# bASEpLATE.net
KiCad netlist of a schematic drawn in EAGLE
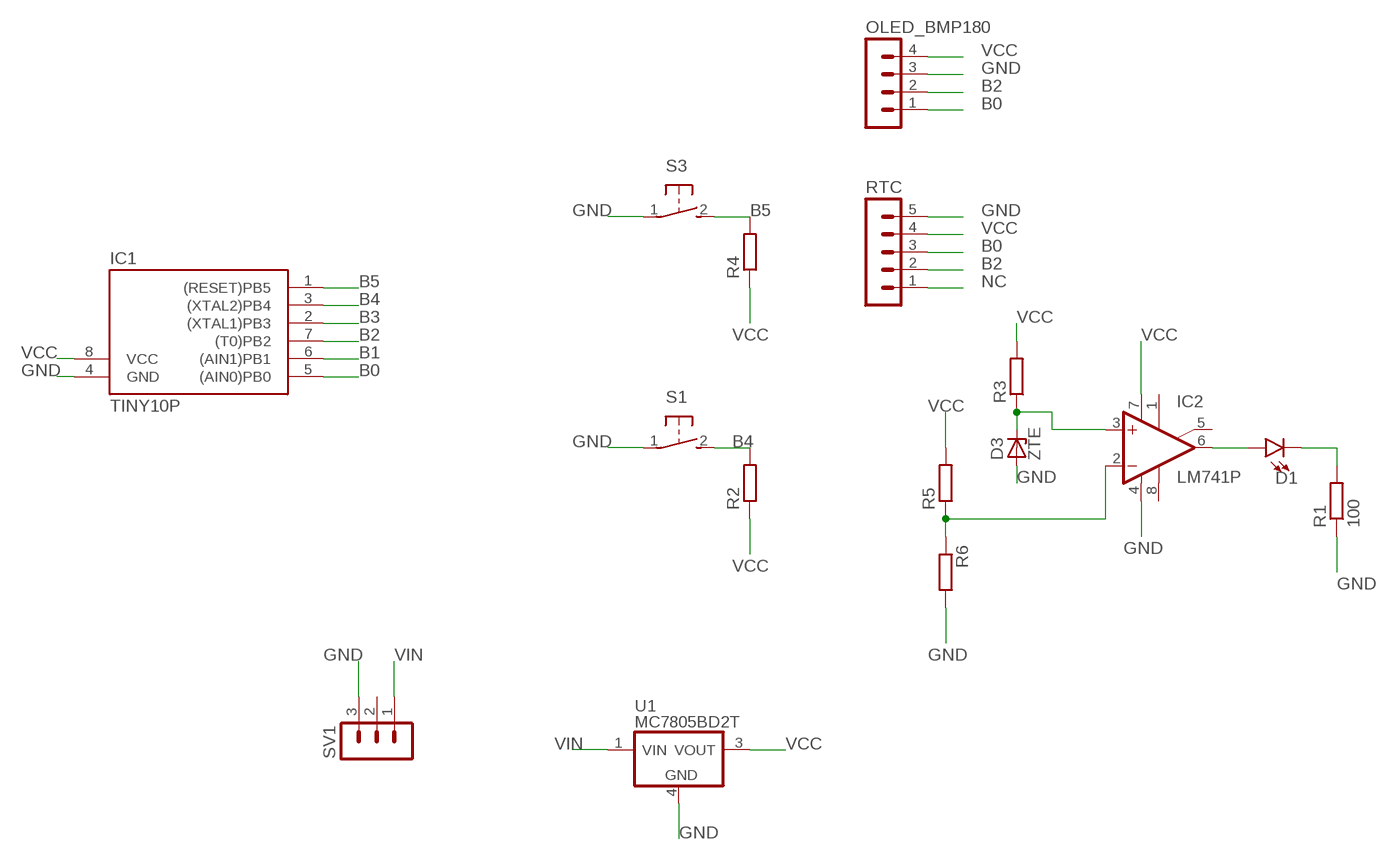
[diagram p0: schematic, sheet 1]

(export (version "E")
  (design (tool "Eeschema 10.0.6"))
  (components
    (comp (ref "D1")
      (value "LED-3MM-NO_SILK")
      (footprint "eagle-import:LED_3MM-NS")
      (libsource (lib "eagle-import") (part "LED-3MM-NO_SILK"))
    )
    (comp (ref "D3")
      (value "ZTE")
      (footprint "eagle-import:DO35Z10")
      (libsource (lib "eagle-import") (part "ZTE"))
    )
    (comp (ref "IC1")
      (value "TINY10P")
      (footprint "eagle-import:DIL08")
      (libsource (lib "eagle-import") (part "TINY10P"))
    )
    (comp (ref "IC2")
      (value "LM741P")
      (footprint "eagle-import:DIL08")
      (libsource (lib "eagle-import") (part "741PLM"))
    )
    (comp (ref "OLED_BMP180")
      (value "MA04-1")
      (footprint "eagle-import:MA04-1")
      (libsource (lib "eagle-import") (part "MA04-1"))
    )
    (comp (ref "R1")
      (value "100")
      (footprint "eagle-import:0204_7")
      (libsource (lib "eagle-import") (part "R-EU_0204/7"))
    )
    (comp (ref "R2")
      (value "R-EU_0204/7")
      (footprint "eagle-import:0204_7")
      (libsource (lib "eagle-import") (part "R-EU_0204/7"))
    )
    (comp (ref "R3")
      (value "R-EU_0204/7")
      (footprint "eagle-import:0204_7")
      (libsource (lib "eagle-import") (part "R-EU_0204/7"))
    )
    (comp (ref "R4")
      (value "R-EU_0204/7")
      (footprint "eagle-import:0204_7")
      (libsource (lib "eagle-import") (part "R-EU_0204/7"))
    )
    (comp (ref "R5")
      (value "R-EU_0204/7")
      (footprint "eagle-import:0204_7")
      (libsource (lib "eagle-import") (part "R-EU_0204/7"))
    )
    (comp (ref "R6")
      (value "R-EU_0204/7")
      (footprint "eagle-import:0204_7")
      (libsource (lib "eagle-import") (part "R-EU_0204/7"))
    )
    (comp (ref "RTC")
      (value "MA05-1")
      (footprint "eagle-import:MA05-1")
      (libsource (lib "eagle-import") (part "MA05-1"))
    )
    (comp (ref "S1")
      (value "31-XX")
      (footprint "eagle-import:B3F-31XX")
      (fields (field (name "MPN") "B3F-3100"))
      (libsource (lib "eagle-import") (part "31-XX"))
    )
    (comp (ref "S3")
      (value "31-XX")
      (footprint "eagle-import:B3F-31XX")
      (fields (field (name "MPN") "B3F-3100"))
      (libsource (lib "eagle-import") (part "31-XX"))
    )
    (comp (ref "SV1")
      (value "MA03-1")
      (footprint "eagle-import:MA03-1")
      (libsource (lib "eagle-import") (part "MA03-1"))
    )
    (comp (ref "U1")
      (value "MC7805BD2T")
      (footprint "eagle-import:D2PAK-3")
      (libsource (lib "eagle-import") (part "MC78D2T05B"))
    )
  )
  (nets
    (net (code "1") (name "/B0") (class "Default")
      (node (ref "IC1") (pin "5") (pinfunction "(AIN0)PB0_5") (pintype "bidirectional"))
      (node (ref "OLED_BMP180") (pin "1") (pinfunction "1_1") (pintype "passive"))
      (node (ref "RTC") (pin "3") (pinfunction "3_3") (pintype "passive"))
    )
    (net (code "2") (name "/B1") (class "Default")
      (node (ref "IC1") (pin "6") (pinfunction "(AIN1)PB1_6") (pintype "bidirectional"))
    )
    (net (code "3") (name "/B2") (class "Default")
      (node (ref "IC1") (pin "7") (pinfunction "(T0)PB2_7") (pintype "bidirectional"))
      (node (ref "OLED_BMP180") (pin "2") (pinfunction "2_2") (pintype "passive"))
      (node (ref "RTC") (pin "2") (pinfunction "2_2") (pintype "passive"))
    )
    (net (code "4") (name "/B3") (class "Default")
      (node (ref "IC1") (pin "2") (pinfunction "(XTAL1)PB3_2") (pintype "bidirectional"))
    )
    (net (code "5") (name "/B4") (class "Default")
      (node (ref "IC1") (pin "3") (pinfunction "(XTAL2)PB4_3") (pintype "bidirectional"))
      (node (ref "R2") (pin "2") (pinfunction "2_2") (pintype "passive"))
      (node (ref "S1") (pin "2") (pinfunction "S_2") (pintype "passive"))
    )
    (net (code "6") (name "/B5") (class "Default")
      (node (ref "IC1") (pin "1") (pinfunction "(RESET)PB5_1") (pintype "bidirectional"))
      (node (ref "R4") (pin "2") (pinfunction "2_2") (pintype "passive"))
      (node (ref "S3") (pin "2") (pinfunction "S_2") (pintype "passive"))
    )
    (net (code "7") (name "/GND") (class "Default")
      (node (ref "D3") (pin "A") (pinfunction "A_A") (pintype "passive"))
      (node (ref "IC1") (pin "4") (pinfunction "GND_4") (pintype "power_in"))
      (node (ref "IC2") (pin "4") (pinfunction "V-_4") (pintype "power_in"))
      (node (ref "OLED_BMP180") (pin "3") (pinfunction "3_3") (pintype "passive"))
      (node (ref "R1") (pin "1") (pinfunction "1_1") (pintype "passive"))
      (node (ref "R6") (pin "2") (pinfunction "2_2") (pintype "passive"))
      (node (ref "RTC") (pin "5") (pinfunction "5_5") (pintype "passive"))
      (node (ref "S1") (pin "1") (pinfunction "P_1") (pintype "passive"))
      (node (ref "S3") (pin "1") (pinfunction "P_1") (pintype "passive"))
      (node (ref "SV1") (pin "3") (pinfunction "3_3") (pintype "passive"))
      (node (ref "U1") (pin "4") (pinfunction "GND_4") (pintype "power_in"))
    )
    (net (code "8") (name "/NC") (class "Default")
      (node (ref "RTC") (pin "1") (pinfunction "1_1") (pintype "passive"))
    )
    (net (code "9") (name "/VCC") (class "Default")
      (node (ref "IC1") (pin "8") (pinfunction "VCC_8") (pintype "power_in"))
      (node (ref "IC2") (pin "7") (pinfunction "V+_7") (pintype "power_in"))
      (node (ref "OLED_BMP180") (pin "4") (pinfunction "4_4") (pintype "passive"))
      (node (ref "R2") (pin "1") (pinfunction "1_1") (pintype "passive"))
      (node (ref "R3") (pin "2") (pinfunction "2_2") (pintype "passive"))
      (node (ref "R4") (pin "1") (pinfunction "1_1") (pintype "passive"))
      (node (ref "R5") (pin "2") (pinfunction "2_2") (pintype "passive"))
      (node (ref "RTC") (pin "4") (pinfunction "4_4") (pintype "passive"))
      (node (ref "U1") (pin "3") (pinfunction "VOUT_3") (pintype "power_in"))
    )
    (net (code "10") (name "/VIN") (class "Default")
      (node (ref "SV1") (pin "1") (pinfunction "1_1") (pintype "passive"))
      (node (ref "U1") (pin "1") (pinfunction "VIN_1") (pintype "power_in"))
    )
    (net (code "11") (name "Net-(D1-C)") (class "Default")
      (node (ref "D1") (pin "K") (pinfunction "C_K") (pintype "passive"))
      (node (ref "R1") (pin "2") (pinfunction "2_2") (pintype "passive"))
    )
    (net (code "12") (name "Net-(IC2-+IN)") (class "Default")
      (node (ref "D3") (pin "C") (pinfunction "C_C") (pintype "passive"))
      (node (ref "IC2") (pin "3") (pinfunction "+IN_3") (pintype "input"))
      (node (ref "R3") (pin "1") (pinfunction "1_1") (pintype "passive"))
    )
    (net (code "13") (name "Net-(IC2--IN)") (class "Default")
      (node (ref "IC2") (pin "2") (pinfunction "-IN_2") (pintype "input"))
      (node (ref "R5") (pin "1") (pinfunction "1_1") (pintype "passive"))
      (node (ref "R6") (pin "1") (pinfunction "1_1") (pintype "passive"))
    )
    (net (code "14") (name "Net-(IC2-OUT)") (class "Default")
      (node (ref "D1") (pin "A") (pinfunction "A_A") (pintype "passive"))
      (node (ref "IC2") (pin "6") (pinfunction "OUT_6") (pintype "output"))
    )
    (net (code "15") (name "unconnected-(IC2-ON1-Pad1)") (class "Default")
      (node (ref "IC2") (pin "1") (pinfunction "ON1_1") (pintype "passive"))
    )
    (net (code "16") (name "unconnected-(IC2-ON2-Pad5)") (class "Default")
      (node (ref "IC2") (pin "5") (pinfunction "ON2_5") (pintype "passive"))
    )
    (net (code "17") (name "unconnected-(IC2-OPT-Pad8)") (class "Default")
      (node (ref "IC2") (pin "8") (pinfunction "OPT_8") (pintype "passive"))
    )
    (net (code "18") (name "unconnected-(SV1-Pad2)") (class "Default")
      (node (ref "SV1") (pin "2") (pinfunction "2_2") (pintype "passive"))
    )
  )
)
